# board.net
KiCad netlist of a schematic drawn in EAGLE
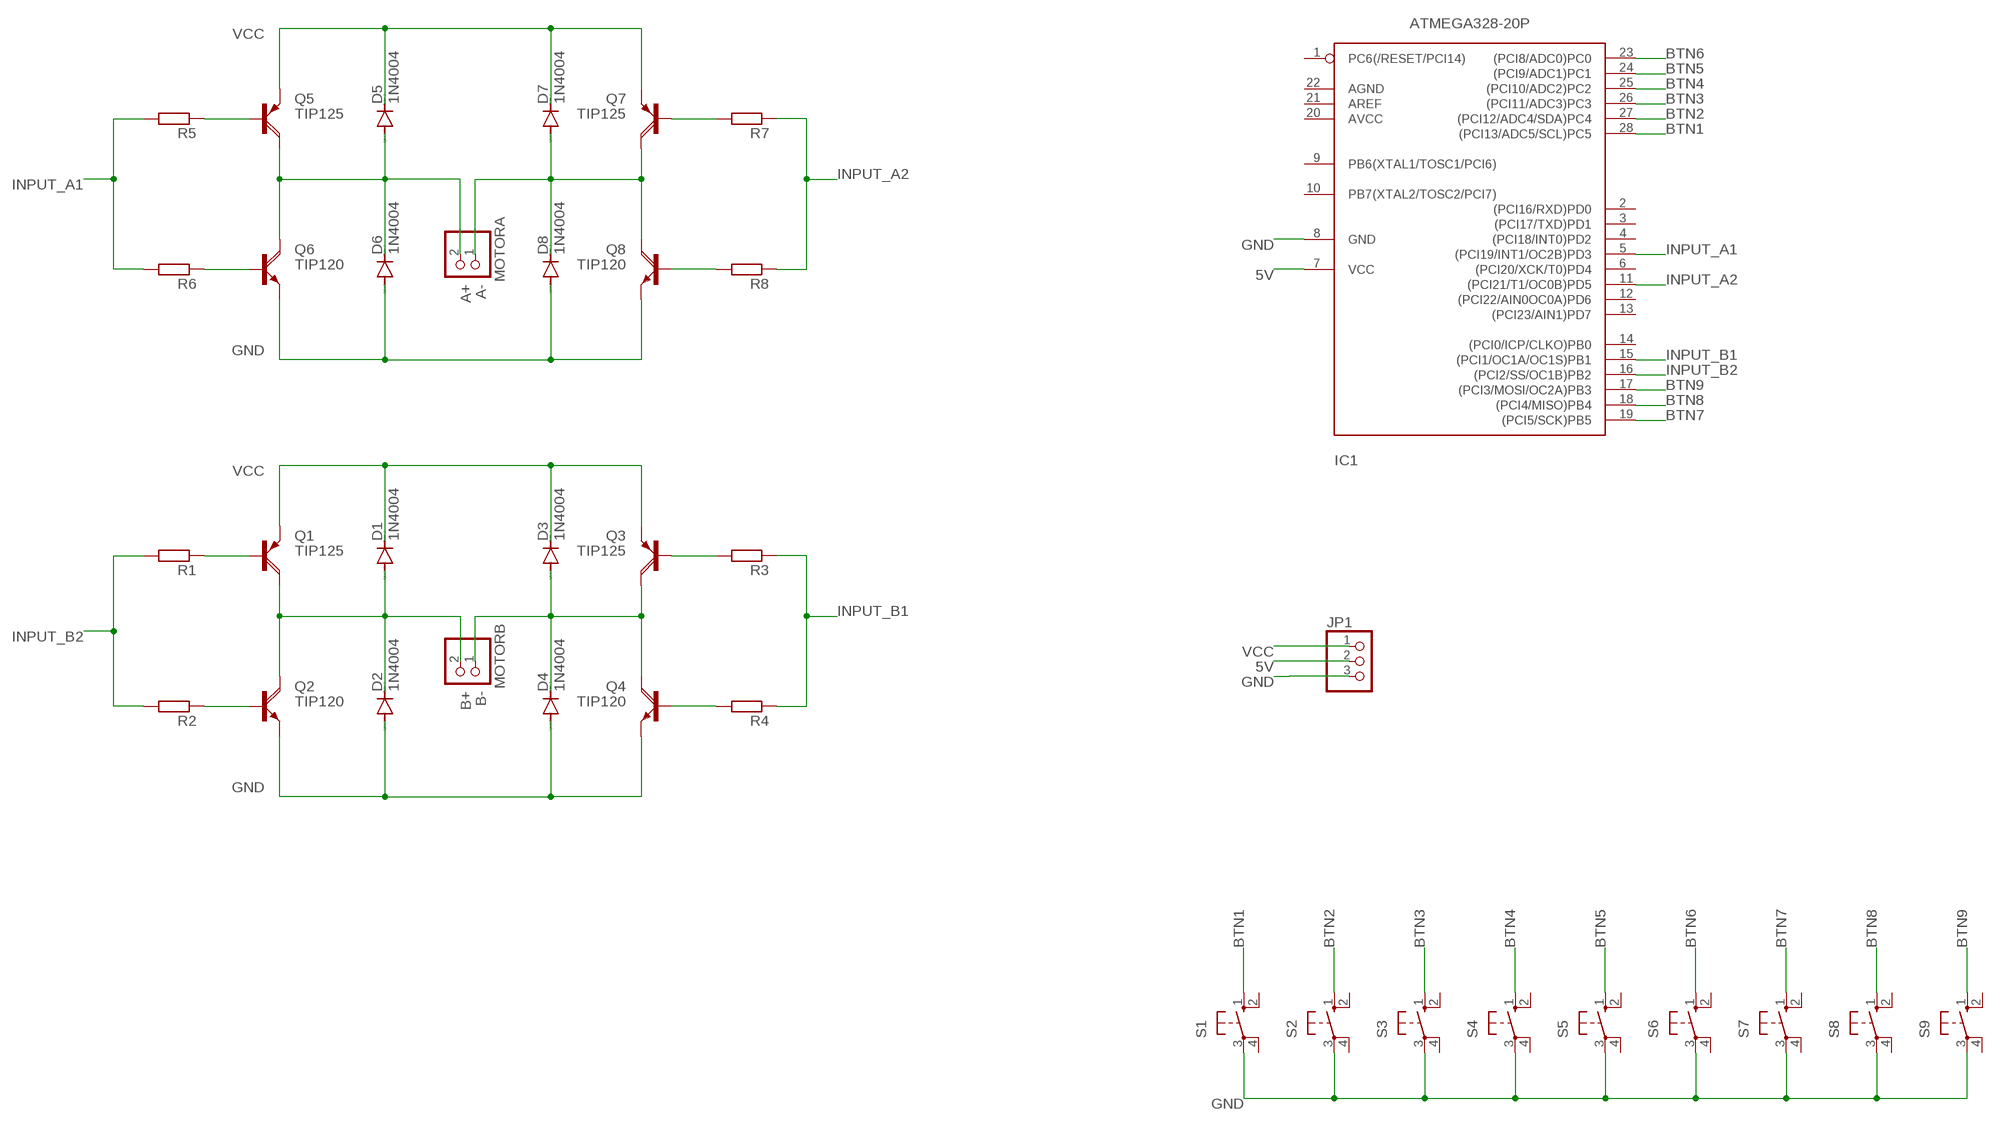
[diagram p0: schematic, sheet 1]

(export (version "E")
  (design (tool "Eeschema 10.0.6"))
  (components
    (comp (ref "D1")
      (value "1N4004")
      (footprint "eagle-import:DO41-10")
      (libsource (lib "eagle-import") (part "1N4004"))
    )
    (comp (ref "D2")
      (value "1N4004")
      (footprint "eagle-import:DO41-10")
      (libsource (lib "eagle-import") (part "1N4004"))
    )
    (comp (ref "D3")
      (value "1N4004")
      (footprint "eagle-import:DO41-10")
      (libsource (lib "eagle-import") (part "1N4004"))
    )
    (comp (ref "D4")
      (value "1N4004")
      (footprint "eagle-import:DO41-10")
      (libsource (lib "eagle-import") (part "1N4004"))
    )
    (comp (ref "D5")
      (value "1N4004")
      (footprint "eagle-import:DO41-10")
      (libsource (lib "eagle-import") (part "1N4004"))
    )
    (comp (ref "D6")
      (value "1N4004")
      (footprint "eagle-import:DO41-10")
      (libsource (lib "eagle-import") (part "1N4004"))
    )
    (comp (ref "D7")
      (value "1N4004")
      (footprint "eagle-import:DO41-10")
      (libsource (lib "eagle-import") (part "1N4004"))
    )
    (comp (ref "D8")
      (value "1N4004")
      (footprint "eagle-import:DO41-10")
      (libsource (lib "eagle-import") (part "1N4004"))
    )
    (comp (ref "IC1")
      (value "ATMEGA328-20P")
      (footprint "eagle-import:DIL28-3")
      (libsource (lib "eagle-import") (part "ATMEGA328P-20"))
    )
    (comp (ref "JP1")
      (value "PINHD-1X3")
      (footprint "eagle-import:1X03")
      (libsource (lib "eagle-import") (part "PINHD-1X3"))
    )
    (comp (ref "MOTORA")
      (value "PINHD-1X2")
      (footprint "eagle-import:1X02")
      (libsource (lib "eagle-import") (part "PINHD-1X2"))
    )
    (comp (ref "MOTORB")
      (value "PINHD-1X2")
      (footprint "eagle-import:1X02")
      (libsource (lib "eagle-import") (part "PINHD-1X2"))
    )
    (comp (ref "Q1")
      (value "TIP125")
      (footprint "eagle-import:TO220AH")
      (libsource (lib "eagle-import") (part "TIP125"))
    )
    (comp (ref "Q2")
      (value "TIP120")
      (footprint "eagle-import:TO220AH")
      (libsource (lib "eagle-import") (part "TIP120"))
    )
    (comp (ref "Q3")
      (value "TIP125")
      (footprint "eagle-import:TO220AH")
      (libsource (lib "eagle-import") (part "TIP125"))
    )
    (comp (ref "Q4")
      (value "TIP120")
      (footprint "eagle-import:TO220AH")
      (libsource (lib "eagle-import") (part "TIP120"))
    )
    (comp (ref "Q5")
      (value "TIP125")
      (footprint "eagle-import:TO220AH")
      (libsource (lib "eagle-import") (part "TIP125"))
    )
    (comp (ref "Q6")
      (value "TIP120")
      (footprint "eagle-import:TO220AH")
      (libsource (lib "eagle-import") (part "TIP120"))
    )
    (comp (ref "Q7")
      (value "TIP125")
      (footprint "eagle-import:TO220AH")
      (libsource (lib "eagle-import") (part "TIP125"))
    )
    (comp (ref "Q8")
      (value "TIP120")
      (footprint "eagle-import:TO220AH")
      (libsource (lib "eagle-import") (part "TIP120"))
    )
    (comp (ref "R1")
      (value "R-EU_0204/7")
      (footprint "eagle-import:0204_7")
      (libsource (lib "eagle-import") (part "R-EU_0204/7"))
    )
    (comp (ref "R2")
      (value "R-EU_0204/7")
      (footprint "eagle-import:0204_7")
      (libsource (lib "eagle-import") (part "R-EU_0204/7"))
    )
    (comp (ref "R3")
      (value "R-EU_0204/7")
      (footprint "eagle-import:0204_7")
      (libsource (lib "eagle-import") (part "R-EU_0204/7"))
    )
    (comp (ref "R4")
      (value "R-EU_0204/7")
      (footprint "eagle-import:0204_7")
      (libsource (lib "eagle-import") (part "R-EU_0204/7"))
    )
    (comp (ref "R5")
      (value "R-EU_0204/7")
      (footprint "eagle-import:0204_7")
      (libsource (lib "eagle-import") (part "R-EU_0204/7"))
    )
    (comp (ref "R6")
      (value "R-EU_0204/7")
      (footprint "eagle-import:0204_7")
      (libsource (lib "eagle-import") (part "R-EU_0204/7"))
    )
    (comp (ref "R7")
      (value "R-EU_0204/7")
      (footprint "eagle-import:0204_7")
      (libsource (lib "eagle-import") (part "R-EU_0204/7"))
    )
    (comp (ref "R8")
      (value "R-EU_0204/7")
      (footprint "eagle-import:0204_7")
      (libsource (lib "eagle-import") (part "R-EU_0204/7"))
    )
    (comp (ref "S1")
      (value "10-XX")
      (footprint "eagle-import:B3F-10XX")
      (fields (field (name "MPN") "B3F-1000"))
      (libsource (lib "eagle-import") (part "10-XX"))
    )
    (comp (ref "S2")
      (value "10-XX")
      (footprint "eagle-import:B3F-10XX")
      (fields (field (name "MPN") "B3F-1000"))
      (libsource (lib "eagle-import") (part "10-XX"))
    )
    (comp (ref "S3")
      (value "10-XX")
      (footprint "eagle-import:B3F-10XX")
      (fields (field (name "MPN") "B3F-1000"))
      (libsource (lib "eagle-import") (part "10-XX"))
    )
    (comp (ref "S4")
      (value "10-XX")
      (footprint "eagle-import:B3F-10XX")
      (fields (field (name "MPN") "B3F-1000"))
      (libsource (lib "eagle-import") (part "10-XX"))
    )
    (comp (ref "S5")
      (value "10-XX")
      (footprint "eagle-import:B3F-10XX")
      (fields (field (name "MPN") "B3F-1000"))
      (libsource (lib "eagle-import") (part "10-XX"))
    )
    (comp (ref "S6")
      (value "10-XX")
      (footprint "eagle-import:B3F-10XX")
      (fields (field (name "MPN") "B3F-1000"))
      (libsource (lib "eagle-import") (part "10-XX"))
    )
    (comp (ref "S7")
      (value "10-XX")
      (footprint "eagle-import:B3F-10XX")
      (fields (field (name "MPN") "B3F-1000"))
      (libsource (lib "eagle-import") (part "10-XX"))
    )
    (comp (ref "S8")
      (value "10-XX")
      (footprint "eagle-import:B3F-10XX")
      (fields (field (name "MPN") "B3F-1000"))
      (libsource (lib "eagle-import") (part "10-XX"))
    )
    (comp (ref "S9")
      (value "10-XX")
      (footprint "eagle-import:B3F-10XX")
      (fields (field (name "MPN") "B3F-1000"))
      (libsource (lib "eagle-import") (part "10-XX"))
    )
  )
  (nets
    (net (code "1") (name "/5V") (class "Default")
      (node (ref "IC1") (pin "7") (pinfunction "VCC_7") (pintype "bidirectional"))
      (node (ref "JP1") (pin "2") (pinfunction "2_2") (pintype "passive"))
    )
    (net (code "2") (name "/A+") (class "Default")
      (node (ref "D5") (pin "A") (pinfunction "A_A") (pintype "passive"))
      (node (ref "D6") (pin "C") (pinfunction "C_C") (pintype "passive"))
      (node (ref "MOTORA") (pin "2") (pinfunction "2_2") (pintype "passive"))
      (node (ref "Q5") (pin "C") (pinfunction "C_C") (pintype "passive"))
      (node (ref "Q6") (pin "C") (pinfunction "C_C") (pintype "passive"))
    )
    (net (code "3") (name "/A-") (class "Default")
      (node (ref "D7") (pin "A") (pinfunction "A_A") (pintype "passive"))
      (node (ref "D8") (pin "C") (pinfunction "C_C") (pintype "passive"))
      (node (ref "MOTORA") (pin "1") (pinfunction "1_1") (pintype "passive"))
      (node (ref "Q7") (pin "C") (pinfunction "C_C") (pintype "passive"))
      (node (ref "Q8") (pin "C") (pinfunction "C_C") (pintype "passive"))
    )
    (net (code "4") (name "/B+") (class "Default")
      (node (ref "D1") (pin "A") (pinfunction "A_A") (pintype "passive"))
      (node (ref "D2") (pin "C") (pinfunction "C_C") (pintype "passive"))
      (node (ref "MOTORB") (pin "2") (pinfunction "2_2") (pintype "passive"))
      (node (ref "Q1") (pin "C") (pinfunction "C_C") (pintype "passive"))
      (node (ref "Q2") (pin "C") (pinfunction "C_C") (pintype "passive"))
    )
    (net (code "5") (name "/B-") (class "Default")
      (node (ref "D3") (pin "A") (pinfunction "A_A") (pintype "passive"))
      (node (ref "D4") (pin "C") (pinfunction "C_C") (pintype "passive"))
      (node (ref "MOTORB") (pin "1") (pinfunction "1_1") (pintype "passive"))
      (node (ref "Q3") (pin "C") (pinfunction "C_C") (pintype "passive"))
      (node (ref "Q4") (pin "C") (pinfunction "C_C") (pintype "passive"))
    )
    (net (code "6") (name "/BTN1") (class "Default")
      (node (ref "IC1") (pin "28") (pinfunction "(PCI13/ADC5/SCL)PC5_28") (pintype "bidirectional"))
      (node (ref "S1") (pin "1") (pinfunction "S_1") (pintype "passive"))
    )
    (net (code "7") (name "/BTN2") (class "Default")
      (node (ref "IC1") (pin "27") (pinfunction "(PCI12/ADC4/SDA)PC4_27") (pintype "bidirectional"))
      (node (ref "S2") (pin "1") (pinfunction "S_1") (pintype "passive"))
    )
    (net (code "8") (name "/BTN3") (class "Default")
      (node (ref "IC1") (pin "26") (pinfunction "(PCI11/ADC3)PC3_26") (pintype "bidirectional"))
      (node (ref "S3") (pin "1") (pinfunction "S_1") (pintype "passive"))
    )
    (net (code "9") (name "/BTN4") (class "Default")
      (node (ref "IC1") (pin "25") (pinfunction "(PCI10/ADC2)PC2_25") (pintype "bidirectional"))
      (node (ref "S4") (pin "1") (pinfunction "S_1") (pintype "passive"))
    )
    (net (code "10") (name "/BTN5") (class "Default")
      (node (ref "IC1") (pin "24") (pinfunction "(PCI9/ADC1)PC1_24") (pintype "bidirectional"))
      (node (ref "S5") (pin "1") (pinfunction "S_1") (pintype "passive"))
    )
    (net (code "11") (name "/BTN6") (class "Default")
      (node (ref "IC1") (pin "23") (pinfunction "(PCI8/ADC0)PC0_23") (pintype "bidirectional"))
      (node (ref "S6") (pin "1") (pinfunction "S_1") (pintype "passive"))
    )
    (net (code "12") (name "/BTN7") (class "Default")
      (node (ref "IC1") (pin "19") (pinfunction "(PCI5/SCK)PB5_19") (pintype "bidirectional"))
      (node (ref "S7") (pin "1") (pinfunction "S_1") (pintype "passive"))
    )
    (net (code "13") (name "/BTN8") (class "Default")
      (node (ref "IC1") (pin "18") (pinfunction "(PCI4/MISO)PB4_18") (pintype "bidirectional"))
      (node (ref "S8") (pin "1") (pinfunction "S_1") (pintype "passive"))
    )
    (net (code "14") (name "/BTN9") (class "Default")
      (node (ref "IC1") (pin "17") (pinfunction "(PCI3/MOSI/OC2A)PB3_17") (pintype "bidirectional"))
      (node (ref "S9") (pin "1") (pinfunction "S_1") (pintype "passive"))
    )
    (net (code "15") (name "/GND") (class "Default")
      (node (ref "D2") (pin "A") (pinfunction "A_A") (pintype "passive"))
      (node (ref "D4") (pin "A") (pinfunction "A_A") (pintype "passive"))
      (node (ref "D6") (pin "A") (pinfunction "A_A") (pintype "passive"))
      (node (ref "D8") (pin "A") (pinfunction "A_A") (pintype "passive"))
      (node (ref "IC1") (pin "8") (pinfunction "GND_8") (pintype "bidirectional"))
      (node (ref "JP1") (pin "3") (pinfunction "3_3") (pintype "passive"))
      (node (ref "Q2") (pin "E") (pinfunction "E_E") (pintype "passive"))
      (node (ref "Q4") (pin "E") (pinfunction "E_E") (pintype "passive"))
      (node (ref "Q6") (pin "E") (pinfunction "E_E") (pintype "passive"))
      (node (ref "Q8") (pin "E") (pinfunction "E_E") (pintype "passive"))
      (node (ref "S1") (pin "3") (pinfunction "P_3") (pintype "passive"))
      (node (ref "S2") (pin "3") (pinfunction "P_3") (pintype "passive"))
      (node (ref "S3") (pin "3") (pinfunction "P_3") (pintype "passive"))
      (node (ref "S4") (pin "3") (pinfunction "P_3") (pintype "passive"))
      (node (ref "S5") (pin "3") (pinfunction "P_3") (pintype "passive"))
      (node (ref "S6") (pin "3") (pinfunction "P_3") (pintype "passive"))
      (node (ref "S7") (pin "3") (pinfunction "P_3") (pintype "passive"))
      (node (ref "S8") (pin "3") (pinfunction "P_3") (pintype "passive"))
      (node (ref "S9") (pin "3") (pinfunction "P_3") (pintype "passive"))
    )
    (net (code "16") (name "/INPUT_A1") (class "Default")
      (node (ref "IC1") (pin "5") (pinfunction "(PCI19/INT1/OC2B)PD3_5") (pintype "bidirectional"))
      (node (ref "R5") (pin "2") (pinfunction "2_2") (pintype "passive"))
      (node (ref "R6") (pin "2") (pinfunction "2_2") (pintype "passive"))
    )
    (net (code "17") (name "/INPUT_A2") (class "Default")
      (node (ref "IC1") (pin "11") (pinfunction "(PCI21/T1/OC0B)PD5_11") (pintype "bidirectional"))
      (node (ref "R7") (pin "1") (pinfunction "1_1") (pintype "passive"))
      (node (ref "R8") (pin "1") (pinfunction "1_1") (pintype "passive"))
    )
    (net (code "18") (name "/INPUT_B1") (class "Default")
      (node (ref "IC1") (pin "15") (pinfunction "(PCI1/OC1A/OC1S)PB1_15") (pintype "bidirectional"))
      (node (ref "R3") (pin "1") (pinfunction "1_1") (pintype "passive"))
      (node (ref "R4") (pin "1") (pinfunction "1_1") (pintype "passive"))
    )
    (net (code "19") (name "/INPUT_B2") (class "Default")
      (node (ref "IC1") (pin "16") (pinfunction "(PCI2/SS/OC1B)PB2_16") (pintype "bidirectional"))
      (node (ref "R1") (pin "2") (pinfunction "2_2") (pintype "passive"))
      (node (ref "R2") (pin "2") (pinfunction "2_2") (pintype "passive"))
    )
    (net (code "20") (name "/VCC") (class "Default")
      (node (ref "D1") (pin "C") (pinfunction "C_C") (pintype "passive"))
      (node (ref "D3") (pin "C") (pinfunction "C_C") (pintype "passive"))
      (node (ref "D5") (pin "C") (pinfunction "C_C") (pintype "passive"))
      (node (ref "D7") (pin "C") (pinfunction "C_C") (pintype "passive"))
      (node (ref "JP1") (pin "1") (pinfunction "1_1") (pintype "passive"))
      (node (ref "Q1") (pin "E") (pinfunction "E_E") (pintype "passive"))
      (node (ref "Q3") (pin "E") (pinfunction "E_E") (pintype "passive"))
      (node (ref "Q5") (pin "E") (pinfunction "E_E") (pintype "passive"))
      (node (ref "Q7") (pin "E") (pinfunction "E_E") (pintype "passive"))
    )
    (net (code "21") (name "Net-(Q1-PadB)") (class "Default")
      (node (ref "Q1") (pin "B") (pinfunction "B_B") (pintype "passive"))
      (node (ref "R1") (pin "1") (pinfunction "1_1") (pintype "passive"))
    )
    (net (code "22") (name "Net-(Q2-PadB)") (class "Default")
      (node (ref "Q2") (pin "B") (pinfunction "B_B") (pintype "passive"))
      (node (ref "R2") (pin "1") (pinfunction "1_1") (pintype "passive"))
    )
    (net (code "23") (name "Net-(Q3-PadB)") (class "Default")
      (node (ref "Q3") (pin "B") (pinfunction "B_B") (pintype "passive"))
      (node (ref "R3") (pin "2") (pinfunction "2_2") (pintype "passive"))
    )
    (net (code "24") (name "Net-(Q4-PadB)") (class "Default")
      (node (ref "Q4") (pin "B") (pinfunction "B_B") (pintype "passive"))
      (node (ref "R4") (pin "2") (pinfunction "2_2") (pintype "passive"))
    )
    (net (code "25") (name "Net-(Q5-PadB)") (class "Default")
      (node (ref "Q5") (pin "B") (pinfunction "B_B") (pintype "passive"))
      (node (ref "R5") (pin "1") (pinfunction "1_1") (pintype "passive"))
    )
    (net (code "26") (name "Net-(Q6-PadB)") (class "Default")
      (node (ref "Q6") (pin "B") (pinfunction "B_B") (pintype "passive"))
      (node (ref "R6") (pin "1") (pinfunction "1_1") (pintype "passive"))
    )
    (net (code "27") (name "Net-(Q7-PadB)") (class "Default")
      (node (ref "Q7") (pin "B") (pinfunction "B_B") (pintype "passive"))
      (node (ref "R7") (pin "2") (pinfunction "2_2") (pintype "passive"))
    )
    (net (code "28") (name "Net-(Q8-PadB)") (class "Default")
      (node (ref "Q8") (pin "B") (pinfunction "B_B") (pintype "passive"))
      (node (ref "R8") (pin "2") (pinfunction "2_2") (pintype "passive"))
    )
    (net (code "29") (name "unconnected-(IC1-(PCI0{slash}ICP{slash}CLKO)PB0-Pad14)") (class "Default")
      (node (ref "IC1") (pin "14") (pinfunction "(PCI0/ICP/CLKO)PB0_14") (pintype "bidirectional"))
    )
    (net (code "30") (name "unconnected-(IC1-(PCI16{slash}RXD)PD0-Pad2)") (class "Default")
      (node (ref "IC1") (pin "2") (pinfunction "(PCI16/RXD)PD0_2") (pintype "bidirectional"))
    )
    (net (code "31") (name "unconnected-(IC1-(PCI17{slash}TXD)PD1-Pad3)") (class "Default")
      (node (ref "IC1") (pin "3") (pinfunction "(PCI17/TXD)PD1_3") (pintype "bidirectional"))
    )
    (net (code "32") (name "unconnected-(IC1-(PCI18{slash}INT0)PD2-Pad4)") (class "Default")
      (node (ref "IC1") (pin "4") (pinfunction "(PCI18/INT0)PD2_4") (pintype "bidirectional"))
    )
    (net (code "33") (name "unconnected-(IC1-(PCI20{slash}XCK{slash}T0)PD4-Pad6)") (class "Default")
      (node (ref "IC1") (pin "6") (pinfunction "(PCI20/XCK/T0)PD4_6") (pintype "bidirectional"))
    )
    (net (code "34") (name "unconnected-(IC1-(PCI22{slash}AIN0OC0A)PD6-Pad12)") (class "Default")
      (node (ref "IC1") (pin "12") (pinfunction "(PCI22/AIN0OC0A)PD6_12") (pintype "bidirectional"))
    )
    (net (code "35") (name "unconnected-(IC1-(PCI23{slash}AIN1)PD7-Pad13)") (class "Default")
      (node (ref "IC1") (pin "13") (pinfunction "(PCI23/AIN1)PD7_13") (pintype "bidirectional"))
    )
    (net (code "36") (name "unconnected-(IC1-AGND-Pad22)") (class "Default")
      (node (ref "IC1") (pin "22") (pinfunction "AGND_22") (pintype "bidirectional"))
    )
    (net (code "37") (name "unconnected-(IC1-AREF-Pad21)") (class "Default")
      (node (ref "IC1") (pin "21") (pinfunction "AREF_21") (pintype "bidirectional"))
    )
    (net (code "38") (name "unconnected-(IC1-AVCC-Pad20)") (class "Default")
      (node (ref "IC1") (pin "20") (pinfunction "AVCC_20") (pintype "bidirectional"))
    )
    (net (code "39") (name "unconnected-(IC1-PB6(XTAL1{slash}TOSC1{slash}PCI6)-Pad9)") (class "Default")
      (node (ref "IC1") (pin "9") (pinfunction "PB6(XTAL1/TOSC1/PCI6)_9") (pintype "bidirectional"))
    )
    (net (code "40") (name "unconnected-(IC1-PB7(XTAL2{slash}TOSC2{slash}PCI7)-Pad10)") (class "Default")
      (node (ref "IC1") (pin "10") (pinfunction "PB7(XTAL2/TOSC2/PCI7)_10") (pintype "bidirectional"))
    )
    (net (code "41") (name "unconnected-(IC1-PC6({slash}RESET{slash}PCI14)-Pad1)") (class "Default")
      (node (ref "IC1") (pin "1") (pinfunction "PC6(/RESET/PCI14)_1") (pintype "bidirectional"))
    )
    (net (code "42") (name "unconnected-(S1-P1-Pad4)") (class "Default")
      (node (ref "S1") (pin "4") (pinfunction "P1_4") (pintype "passive"))
    )
    (net (code "43") (name "unconnected-(S1-S1-Pad2)") (class "Default")
      (node (ref "S1") (pin "2") (pinfunction "S1_2") (pintype "passive"))
    )
    (net (code "44") (name "unconnected-(S2-P1-Pad4)") (class "Default")
      (node (ref "S2") (pin "4") (pinfunction "P1_4") (pintype "passive"))
    )
    (net (code "45") (name "unconnected-(S2-S1-Pad2)") (class "Default")
      (node (ref "S2") (pin "2") (pinfunction "S1_2") (pintype "passive"))
    )
    (net (code "46") (name "unconnected-(S3-P1-Pad4)") (class "Default")
      (node (ref "S3") (pin "4") (pinfunction "P1_4") (pintype "passive"))
    )
    (net (code "47") (name "unconnected-(S3-S1-Pad2)") (class "Default")
      (node (ref "S3") (pin "2") (pinfunction "S1_2") (pintype "passive"))
    )
    (net (code "48") (name "unconnected-(S4-P1-Pad4)") (class "Default")
      (node (ref "S4") (pin "4") (pinfunction "P1_4") (pintype "passive"))
    )
    (net (code "49") (name "unconnected-(S4-S1-Pad2)") (class "Default")
      (node (ref "S4") (pin "2") (pinfunction "S1_2") (pintype "passive"))
    )
    (net (code "50") (name "unconnected-(S5-P1-Pad4)") (class "Default")
      (node (ref "S5") (pin "4") (pinfunction "P1_4") (pintype "passive"))
    )
    (net (code "51") (name "unconnected-(S5-S1-Pad2)") (class "Default")
      (node (ref "S5") (pin "2") (pinfunction "S1_2") (pintype "passive"))
    )
    (net (code "52") (name "unconnected-(S6-P1-Pad4)") (class "Default")
      (node (ref "S6") (pin "4") (pinfunction "P1_4") (pintype "passive"))
    )
    (net (code "53") (name "unconnected-(S6-S1-Pad2)") (class "Default")
      (node (ref "S6") (pin "2") (pinfunction "S1_2") (pintype "passive"))
    )
    (net (code "54") (name "unconnected-(S7-P1-Pad4)") (class "Default")
      (node (ref "S7") (pin "4") (pinfunction "P1_4") (pintype "passive"))
    )
    (net (code "55") (name "unconnected-(S7-S1-Pad2)") (class "Default")
      (node (ref "S7") (pin "2") (pinfunction "S1_2") (pintype "passive"))
    )
    (net (code "56") (name "unconnected-(S8-P1-Pad4)") (class "Default")
      (node (ref "S8") (pin "4") (pinfunction "P1_4") (pintype "passive"))
    )
    (net (code "57") (name "unconnected-(S8-S1-Pad2)") (class "Default")
      (node (ref "S8") (pin "2") (pinfunction "S1_2") (pintype "passive"))
    )
    (net (code "58") (name "unconnected-(S9-P1-Pad4)") (class "Default")
      (node (ref "S9") (pin "4") (pinfunction "P1_4") (pintype "passive"))
    )
    (net (code "59") (name "unconnected-(S9-S1-Pad2)") (class "Default")
      (node (ref "S9") (pin "2") (pinfunction "S1_2") (pintype "passive"))
    )
  )
)
